# w13_atmega328.net
KiCad netlist of a schematic drawn in EAGLE
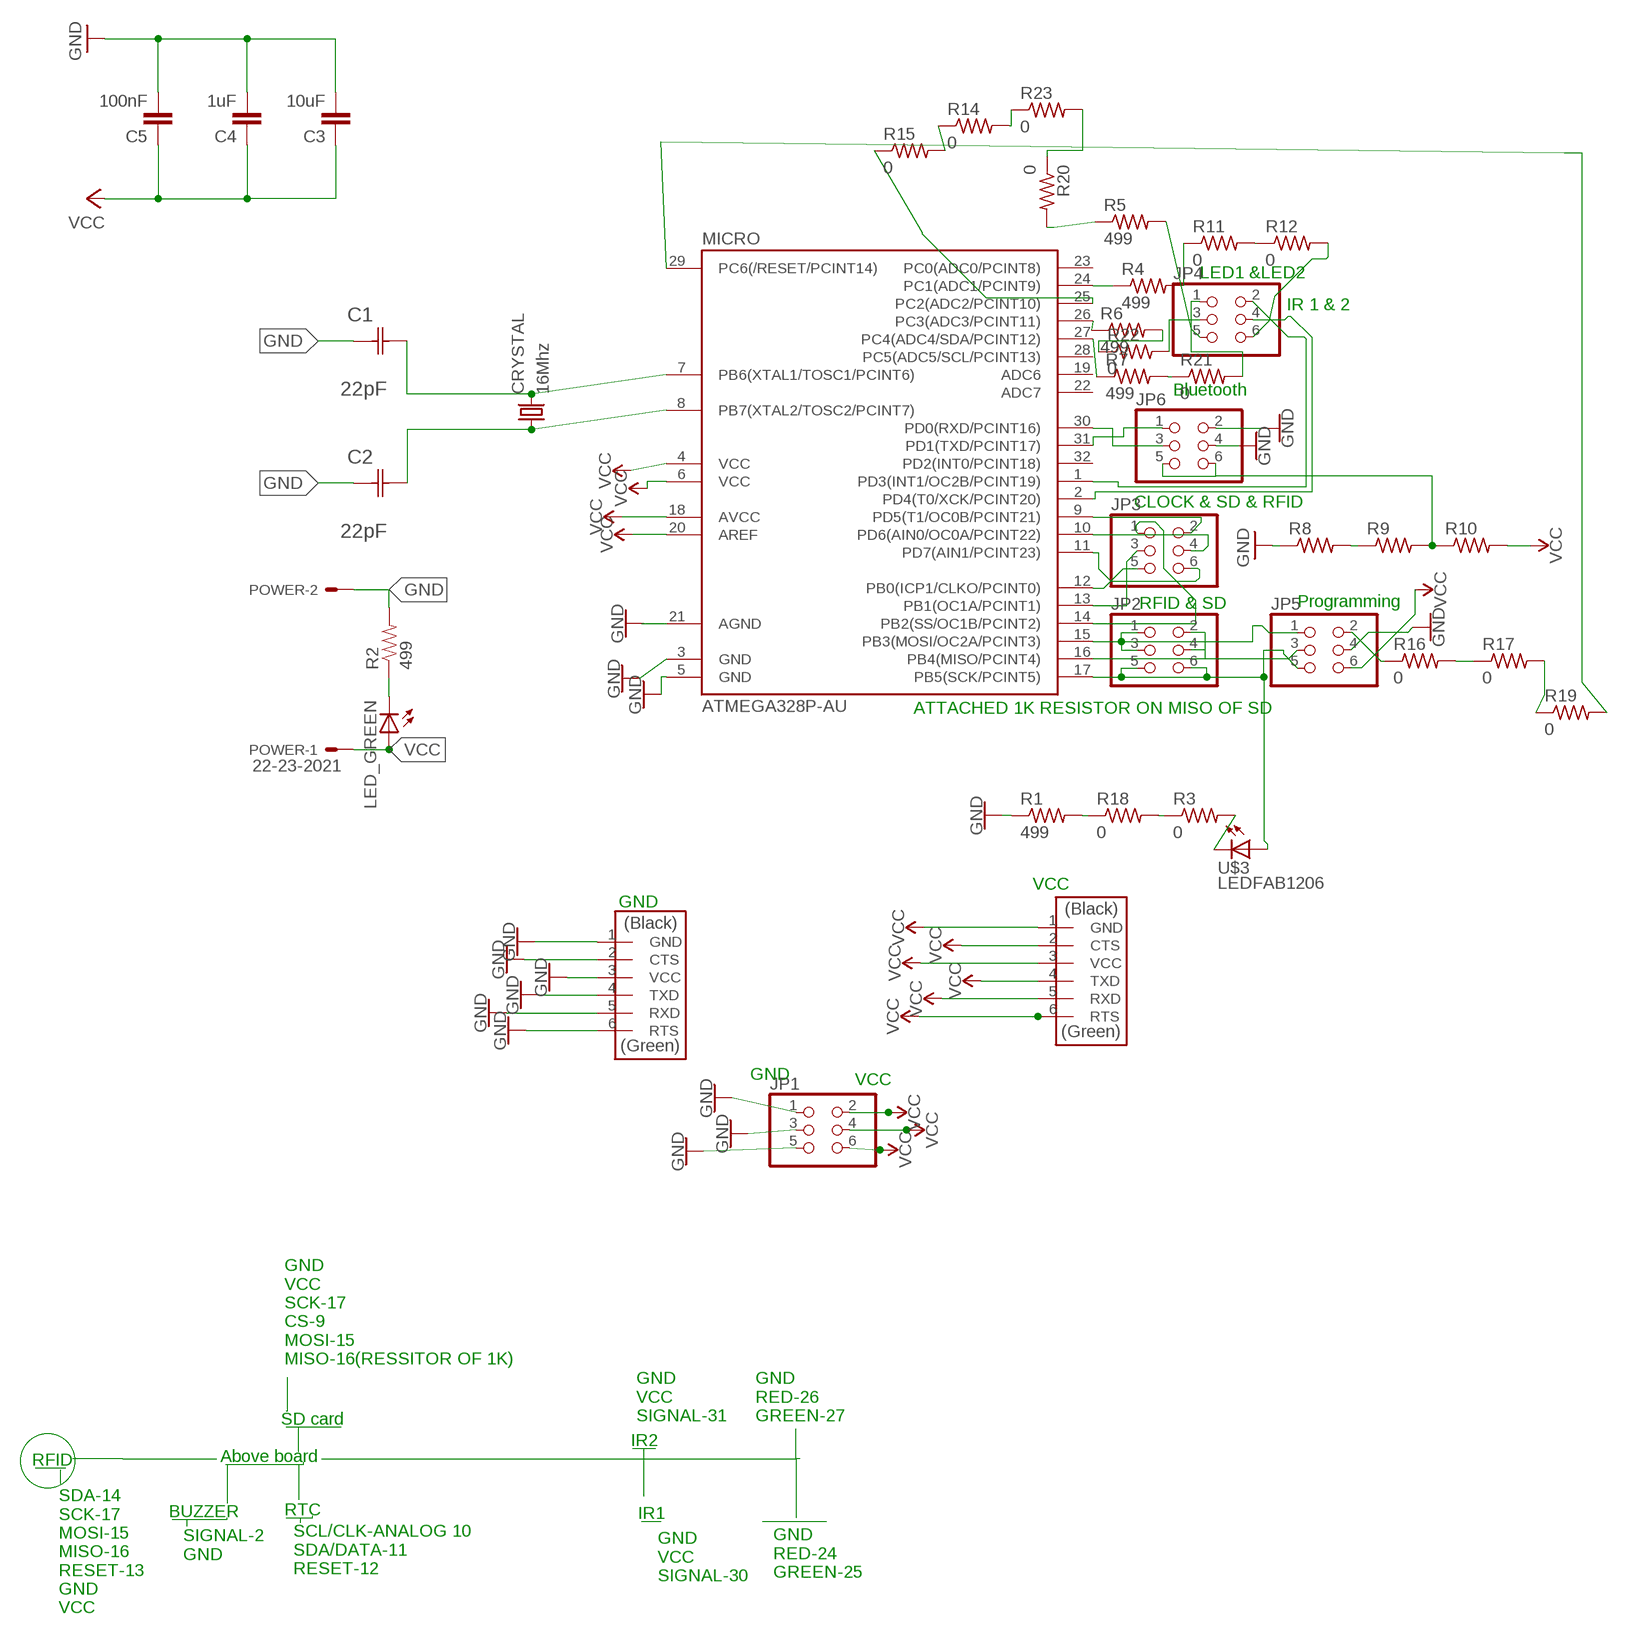
[diagram p0: schematic, sheet 1]

(export (version "E")
  (design (tool "Eeschema 10.0.6"))
  (components
    (comp (ref "C1")
      (value "22pF")
      (footprint "eagle-import:CAPC3216X178N")
      (fields (field (name "MPN") "0612ZC225MAT2A") (field (name "TOLERANCE") "±20%"))
      (libsource (lib "eagle-import") (part "0612ZC225MAT2A"))
    )
    (comp (ref "C2")
      (value "22pF")
      (footprint "eagle-import:CAPC3216X178N")
      (fields (field (name "MPN") "0612ZC225MAT2A") (field (name "TOLERANCE") "±20%"))
      (libsource (lib "eagle-import") (part "0612ZC225MAT2A"))
    )
    (comp (ref "C3")
      (value "10uF")
      (footprint "eagle-import:1206")
      (libsource (lib "eagle-import") (part "CAP1206"))
    )
    (comp (ref "C4")
      (value "1uF")
      (footprint "eagle-import:1206")
      (libsource (lib "eagle-import") (part "CAP1206"))
    )
    (comp (ref "C5")
      (value "100nF")
      (footprint "eagle-import:1206")
      (libsource (lib "eagle-import") (part "CAP1206"))
    )
    (comp (ref "CRYSTAL")
      (value "16Mhz")
      (footprint "eagle-import:CSM-7X-DU")
      (libsource (lib "eagle-import") (part "CSM-7X-DU"))
    )
    (comp (ref "JP1")
      (value "PINHD-2X3-SMD")
      (footprint "eagle-import:2X03SMD")
      (libsource (lib "eagle-import") (part "PINHD-2X3-SMD"))
    )
    (comp (ref "JP2")
      (value "PINHD-2X3-SMD")
      (footprint "eagle-import:2X03SMD")
      (libsource (lib "eagle-import") (part "PINHD-2X3-SMD"))
    )
    (comp (ref "JP3")
      (value "PINHD-2X3-SMD")
      (footprint "eagle-import:2X03SMD")
      (libsource (lib "eagle-import") (part "PINHD-2X3-SMD"))
    )
    (comp (ref "JP4")
      (value "PINHD-2X3-SMD")
      (footprint "eagle-import:2X03SMD")
      (libsource (lib "eagle-import") (part "PINHD-2X3-SMD"))
    )
    (comp (ref "JP5")
      (value "PINHD-2X3-SMD")
      (footprint "eagle-import:2X03SMD")
      (libsource (lib "eagle-import") (part "PINHD-2X3-SMD"))
    )
    (comp (ref "JP6")
      (value "PINHD-2X3-SMD")
      (footprint "eagle-import:2X03SMD")
      (libsource (lib "eagle-import") (part "PINHD-2X3-SMD"))
    )
    (comp (ref "LED_GREEN")
      (value "LED1206")
      (footprint "eagle-import:1206")
      (libsource (lib "eagle-import") (part "LED1206"))
    )
    (comp (ref "MICRO")
      (value "ATMEGA328P-AU")
      (footprint "eagle-import:TQFP32-08")
      (libsource (lib "eagle-import") (part "ATMEGA48/88/168-AU"))
    )
    (comp (ref "POWER")
      (value "22-23-2021")
      (footprint "eagle-import:22-23-2021")
      (fields (field (name "MF") "MOLEX"))
      (libsource (lib "eagle-import") (part "22-23-2021"))
    )
    (comp (ref "R1")
      (value "499")
      (footprint "eagle-import:R1206")
      (libsource (lib "eagle-import") (part "RES-US1206"))
    )
    (comp (ref "R2")
      (value "499")
      (footprint "eagle-import:1206")
      (libsource (lib "eagle-import") (part "RESISTOR1206"))
    )
    (comp (ref "R3")
      (value "0")
      (footprint "eagle-import:R1206FAB")
      (libsource (lib "eagle-import") (part "RES-US1206FAB"))
    )
    (comp (ref "R4")
      (value "499")
      (footprint "eagle-import:R1206FAB")
      (libsource (lib "eagle-import") (part "RES-US1206FAB"))
    )
    (comp (ref "R5")
      (value "499")
      (footprint "eagle-import:R1206FAB")
      (libsource (lib "eagle-import") (part "RES-US1206FAB"))
    )
    (comp (ref "R6")
      (value "499")
      (footprint "eagle-import:R1206FAB")
      (libsource (lib "eagle-import") (part "RES-US1206FAB"))
    )
    (comp (ref "R7")
      (value "499")
      (footprint "eagle-import:R1206FAB")
      (libsource (lib "eagle-import") (part "RES-US1206FAB"))
    )
    (comp (ref "R8")
      (value "RES-US1206FAB")
      (footprint "eagle-import:R1206FAB")
      (libsource (lib "eagle-import") (part "RES-US1206FAB"))
    )
    (comp (ref "R9")
      (value "RES-US1206FAB")
      (footprint "eagle-import:R1206FAB")
      (libsource (lib "eagle-import") (part "RES-US1206FAB"))
    )
    (comp (ref "R10")
      (value "RES-US1206FAB")
      (footprint "eagle-import:R1206FAB")
      (libsource (lib "eagle-import") (part "RES-US1206FAB"))
    )
    (comp (ref "R11")
      (value "0")
      (footprint "eagle-import:R1206FAB")
      (libsource (lib "eagle-import") (part "RES-US1206FAB"))
    )
    (comp (ref "R12")
      (value "0")
      (footprint "eagle-import:R1206FAB")
      (libsource (lib "eagle-import") (part "RES-US1206FAB"))
    )
    (comp (ref "R14")
      (value "0")
      (footprint "eagle-import:R1206FAB")
      (libsource (lib "eagle-import") (part "RES-US1206FAB"))
    )
    (comp (ref "R15")
      (value "0")
      (footprint "eagle-import:R1206FAB")
      (libsource (lib "eagle-import") (part "RES-US1206FAB"))
    )
    (comp (ref "R16")
      (value "0")
      (footprint "eagle-import:R1206FAB")
      (libsource (lib "eagle-import") (part "RES-US1206FAB"))
    )
    (comp (ref "R17")
      (value "0")
      (footprint "eagle-import:R1206FAB")
      (libsource (lib "eagle-import") (part "RES-US1206FAB"))
    )
    (comp (ref "R18")
      (value "0")
      (footprint "eagle-import:R1206FAB")
      (libsource (lib "eagle-import") (part "RES-US1206FAB"))
    )
    (comp (ref "R19")
      (value "0")
      (footprint "eagle-import:R1206FAB")
      (libsource (lib "eagle-import") (part "RES-US1206FAB"))
    )
    (comp (ref "R20")
      (value "0")
      (footprint "eagle-import:R1206FAB")
      (libsource (lib "eagle-import") (part "RES-US1206FAB"))
    )
    (comp (ref "R21")
      (value "0")
      (footprint "eagle-import:R1206FAB")
      (libsource (lib "eagle-import") (part "RES-US1206FAB"))
    )
    (comp (ref "R22")
      (value "0")
      (footprint "eagle-import:R1206FAB")
      (libsource (lib "eagle-import") (part "RES-US1206FAB"))
    )
    (comp (ref "R23")
      (value "0")
      (footprint "eagle-import:R1206FAB")
      (libsource (lib "eagle-import") (part "RES-US1206FAB"))
    )
    (comp (ref "U$1")
      (value "FTDI-SMD-HEADER")
      (footprint "eagle-import:1X06SMD")
      (libsource (lib "eagle-import") (part "FTDI-SMD-HEADER"))
    )
    (comp (ref "U$2")
      (value "FTDI-SMD-HEADER")
      (footprint "eagle-import:1X06SMD")
      (libsource (lib "eagle-import") (part "FTDI-SMD-HEADER"))
    )
    (comp (ref "U$3")
      (value "LEDFAB1206")
      (footprint "eagle-import:LED1206FAB")
      (libsource (lib "eagle-import") (part "LEDFAB1206"))
    )
  )
  (nets
    (net (code "1") (name "GND") (class "Default")
      (node (ref "C1") (pin "1") (pinfunction "C1_1") (pintype "passive"))
      (node (ref "C2") (pin "1") (pinfunction "C1_1") (pintype "passive"))
      (node (ref "C3") (pin "2") (pinfunction "2_2") (pintype "passive"))
      (node (ref "C4") (pin "2") (pinfunction "2_2") (pintype "passive"))
      (node (ref "C5") (pin "2") (pinfunction "2_2") (pintype "passive"))
      (node (ref "JP1") (pin "1") (pinfunction "1_1") (pintype "passive"))
      (node (ref "JP1") (pin "3") (pinfunction "3_3") (pintype "passive"))
      (node (ref "JP1") (pin "5") (pinfunction "5_5") (pintype "passive"))
      (node (ref "JP5") (pin "4") (pinfunction "4_4") (pintype "passive"))
      (node (ref "JP6") (pin "2") (pinfunction "2_2") (pintype "passive"))
      (node (ref "JP6") (pin "4") (pinfunction "4_4") (pintype "passive"))
      (node (ref "MICRO") (pin "3") (pinfunction "GND_3") (pintype "power_in"))
      (node (ref "MICRO") (pin "5") (pinfunction "GND_5") (pintype "power_in"))
      (node (ref "POWER") (pin "2") (pinfunction "S_2") (pintype "passive"))
      (node (ref "R1") (pin "1") (pinfunction "1_1") (pintype "passive"))
      (node (ref "R2") (pin "2") (pinfunction "2_2") (pintype "passive"))
      (node (ref "R8") (pin "1") (pinfunction "1_1") (pintype "passive"))
      (node (ref "U$1") (pin "1") (pinfunction "GND_1") (pintype "bidirectional"))
      (node (ref "U$1") (pin "2") (pinfunction "CTS_2") (pintype "bidirectional"))
      (node (ref "U$1") (pin "3") (pinfunction "VCC_3") (pintype "bidirectional"))
      (node (ref "U$1") (pin "4") (pinfunction "TXD_4") (pintype "bidirectional"))
      (node (ref "U$1") (pin "5") (pinfunction "RXD_5") (pintype "bidirectional"))
      (node (ref "U$1") (pin "6") (pinfunction "RTS_6") (pintype "bidirectional"))
    )
    (net (code "2") (name "Net-(C1-C2)") (class "Default")
      (node (ref "C1") (pin "2") (pinfunction "C2_2") (pintype "passive"))
      (node (ref "CRYSTAL") (pin "2") (pinfunction "2_2") (pintype "passive"))
      (node (ref "MICRO") (pin "7") (pinfunction "PB6(XTAL1/TOSC1/PCINT6)_7") (pintype "bidirectional"))
    )
    (net (code "3") (name "Net-(C2-C2)") (class "Default")
      (node (ref "C2") (pin "2") (pinfunction "C2_2") (pintype "passive"))
      (node (ref "CRYSTAL") (pin "1") (pinfunction "1_1") (pintype "passive"))
      (node (ref "MICRO") (pin "8") (pinfunction "PB7(XTAL2/TOSC2/PCINT7)_8") (pintype "bidirectional"))
    )
    (net (code "4") (name "Net-(JP4-Pad1)") (class "Default")
      (node (ref "JP4") (pin "1") (pinfunction "1_1") (pintype "passive"))
      (node (ref "R21") (pin "2") (pinfunction "2_2") (pintype "passive"))
    )
    (net (code "5") (name "Net-(JP4-Pad3)") (class "Default")
      (node (ref "JP4") (pin "3") (pinfunction "3_3") (pintype "passive"))
      (node (ref "R22") (pin "2") (pinfunction "2_2") (pintype "passive"))
    )
    (net (code "6") (name "Net-(JP4-Pad5)") (class "Default")
      (node (ref "JP4") (pin "5") (pinfunction "5_5") (pintype "passive"))
      (node (ref "R5") (pin "2") (pinfunction "2_2") (pintype "passive"))
    )
    (net (code "7") (name "Net-(JP4-Pad6)") (class "Default")
      (node (ref "JP4") (pin "6") (pinfunction "6_6") (pintype "passive"))
      (node (ref "R12") (pin "2") (pinfunction "2_2") (pintype "passive"))
    )
    (net (code "8") (name "Net-(JP5-Pad2)") (class "Default")
      (node (ref "JP5") (pin "2") (pinfunction "2_2") (pintype "passive"))
      (node (ref "R16") (pin "1") (pinfunction "1_1") (pintype "passive"))
    )
    (net (code "9") (name "Net-(JP6-Pad5)") (class "Default")
      (node (ref "JP6") (pin "5") (pinfunction "5_5") (pintype "passive"))
      (node (ref "JP6") (pin "6") (pinfunction "6_6") (pintype "passive"))
      (node (ref "R10") (pin "1") (pinfunction "1_1") (pintype "passive"))
      (node (ref "R9") (pin "2") (pinfunction "2_2") (pintype "passive"))
    )
    (net (code "10") (name "Net-(LED_GREEN-C)") (class "Default")
      (node (ref "LED_GREEN") (pin "2") (pinfunction "C_2") (pintype "passive"))
      (node (ref "R2") (pin "1") (pinfunction "1_1") (pintype "passive"))
    )
    (net (code "11") (name "Net-(MICRO-PB0(ICP1{slash}CLKO{slash}PCINT0))") (class "Default")
      (node (ref "JP3") (pin "5") (pinfunction "5_5") (pintype "passive"))
      (node (ref "MICRO") (pin "12") (pinfunction "PB0(ICP1/CLKO/PCINT0)_12") (pintype "bidirectional"))
    )
    (net (code "12") (name "Net-(MICRO-PB1(OC1A{slash}PCINT1))") (class "Default")
      (node (ref "JP3") (pin "3") (pinfunction "3_3") (pintype "passive"))
      (node (ref "MICRO") (pin "13") (pinfunction "PB1(OC1A/PCINT1)_13") (pintype "bidirectional"))
    )
    (net (code "13") (name "Net-(MICRO-PB2(SS{slash}OC1B{slash}PCINT2))") (class "Default")
      (node (ref "JP3") (pin "1") (pinfunction "1_1") (pintype "passive"))
      (node (ref "MICRO") (pin "14") (pinfunction "PB2(SS/OC1B/PCINT2)_14") (pintype "bidirectional"))
    )
    (net (code "14") (name "Net-(MICRO-PB3(MOSI{slash}OC2A{slash}PCINT3))") (class "Default")
      (node (ref "JP2") (pin "1") (pinfunction "1_1") (pintype "passive"))
      (node (ref "JP2") (pin "3") (pinfunction "3_3") (pintype "passive"))
      (node (ref "JP5") (pin "1") (pinfunction "1_1") (pintype "passive"))
      (node (ref "MICRO") (pin "15") (pinfunction "PB3(MOSI/OC2A/PCINT3)_15") (pintype "bidirectional"))
    )
    (net (code "15") (name "Net-(MICRO-PB4(MISO{slash}PCINT4))") (class "Default")
      (node (ref "JP2") (pin "2") (pinfunction "2_2") (pintype "passive"))
      (node (ref "JP2") (pin "4") (pinfunction "4_4") (pintype "passive"))
      (node (ref "JP5") (pin "3") (pinfunction "3_3") (pintype "passive"))
      (node (ref "MICRO") (pin "16") (pinfunction "PB4(MISO/PCINT4)_16") (pintype "bidirectional"))
    )
    (net (code "16") (name "Net-(MICRO-PB5(SCK{slash}PCINT5))") (class "Default")
      (node (ref "JP2") (pin "5") (pinfunction "5_5") (pintype "passive"))
      (node (ref "JP2") (pin "6") (pinfunction "6_6") (pintype "passive"))
      (node (ref "JP5") (pin "5") (pinfunction "5_5") (pintype "passive"))
      (node (ref "MICRO") (pin "17") (pinfunction "PB5(SCK/PCINT5)_17") (pintype "bidirectional"))
      (node (ref "U$3") (pin "1") (pinfunction "A_1") (pintype "passive"))
    )
    (net (code "17") (name "Net-(MICRO-PC1(ADC1{slash}PCINT9))") (class "Default")
      (node (ref "MICRO") (pin "24") (pinfunction "PC1(ADC1/PCINT9)_24") (pintype "bidirectional"))
      (node (ref "R4") (pin "1") (pinfunction "1_1") (pintype "passive"))
    )
    (net (code "18") (name "Net-(MICRO-PC2(ADC2{slash}PCINT10))") (class "Default")
      (node (ref "MICRO") (pin "25") (pinfunction "PC2(ADC2/PCINT10)_25") (pintype "bidirectional"))
      (node (ref "R15") (pin "1") (pinfunction "1_1") (pintype "passive"))
    )
    (net (code "19") (name "Net-(MICRO-PC3(ADC3{slash}PCINT11))") (class "Default")
      (node (ref "MICRO") (pin "26") (pinfunction "PC3(ADC3/PCINT11)_26") (pintype "bidirectional"))
      (node (ref "R6") (pin "1") (pinfunction "1_1") (pintype "passive"))
    )
    (net (code "20") (name "Net-(MICRO-PC4(ADC4{slash}SDA{slash}PCINT12))") (class "Default")
      (node (ref "MICRO") (pin "27") (pinfunction "PC4(ADC4/SDA/PCINT12)_27") (pintype "bidirectional"))
      (node (ref "R7") (pin "1") (pinfunction "1_1") (pintype "passive"))
    )
    (net (code "21") (name "Net-(MICRO-PC6({slash}RESET{slash}PCINT14))") (class "Default")
      (node (ref "MICRO") (pin "29") (pinfunction "PC6(/RESET/PCINT14)_29") (pintype "bidirectional"))
      (node (ref "R19") (pin "2") (pinfunction "2_2") (pintype "passive"))
    )
    (net (code "22") (name "Net-(MICRO-PD0(RXD{slash}PCINT16))") (class "Default")
      (node (ref "JP6") (pin "3") (pinfunction "3_3") (pintype "passive"))
      (node (ref "MICRO") (pin "30") (pinfunction "PD0(RXD/PCINT16)_30") (pintype "bidirectional"))
    )
    (net (code "23") (name "Net-(MICRO-PD1(TXD{slash}PCINT17))") (class "Default")
      (node (ref "JP6") (pin "1") (pinfunction "1_1") (pintype "passive"))
      (node (ref "MICRO") (pin "31") (pinfunction "PD1(TXD/PCINT17)_31") (pintype "bidirectional"))
    )
    (net (code "24") (name "Net-(MICRO-PD3(INT1{slash}OC2B{slash}PCINT19))") (class "Default")
      (node (ref "JP4") (pin "2") (pinfunction "2_2") (pintype "passive"))
      (node (ref "MICRO") (pin "1") (pinfunction "PD3(INT1/OC2B/PCINT19)_1") (pintype "bidirectional"))
    )
    (net (code "25") (name "Net-(MICRO-PD4(T0{slash}XCK{slash}PCINT20))") (class "Default")
      (node (ref "JP4") (pin "4") (pinfunction "4_4") (pintype "passive"))
      (node (ref "MICRO") (pin "2") (pinfunction "PD4(T0/XCK/PCINT20)_2") (pintype "bidirectional"))
    )
    (net (code "26") (name "Net-(MICRO-PD5(T1{slash}OC0B{slash}PCINT21))") (class "Default")
      (node (ref "JP3") (pin "2") (pinfunction "2_2") (pintype "passive"))
      (node (ref "MICRO") (pin "9") (pinfunction "PD5(T1/OC0B/PCINT21)_9") (pintype "bidirectional"))
    )
    (net (code "27") (name "Net-(MICRO-PD6(AIN0{slash}OC0A{slash}PCINT22))") (class "Default")
      (node (ref "JP3") (pin "4") (pinfunction "4_4") (pintype "passive"))
      (node (ref "MICRO") (pin "10") (pinfunction "PD6(AIN0/OC0A/PCINT22)_10") (pintype "bidirectional"))
    )
    (net (code "28") (name "Net-(MICRO-PD7(AIN1{slash}PCINT23))") (class "Default")
      (node (ref "JP3") (pin "6") (pinfunction "6_6") (pintype "passive"))
      (node (ref "MICRO") (pin "11") (pinfunction "PD7(AIN1/PCINT23)_11") (pintype "bidirectional"))
    )
    (net (code "29") (name "Net-(R1-Pad2)") (class "Default")
      (node (ref "R1") (pin "2") (pinfunction "2_2") (pintype "passive"))
      (node (ref "R18") (pin "1") (pinfunction "1_1") (pintype "passive"))
    )
    (net (code "30") (name "Net-(R8-Pad2)") (class "Default")
      (node (ref "R8") (pin "2") (pinfunction "2_2") (pintype "passive"))
      (node (ref "R9") (pin "1") (pinfunction "1_1") (pintype "passive"))
    )
    (net (code "31") (name "Net-(R11-Pad1)") (class "Default")
      (node (ref "R11") (pin "1") (pinfunction "1_1") (pintype "passive"))
      (node (ref "R4") (pin "2") (pinfunction "2_2") (pintype "passive"))
    )
    (net (code "32") (name "Net-(R11-Pad2)") (class "Default")
      (node (ref "R11") (pin "2") (pinfunction "2_2") (pintype "passive"))
      (node (ref "R12") (pin "1") (pinfunction "1_1") (pintype "passive"))
    )
    (net (code "33") (name "Net-(R14-Pad1)") (class "Default")
      (node (ref "R14") (pin "1") (pinfunction "1_1") (pintype "passive"))
      (node (ref "R15") (pin "2") (pinfunction "2_2") (pintype "passive"))
    )
    (net (code "34") (name "Net-(R14-Pad2)") (class "Default")
      (node (ref "R14") (pin "2") (pinfunction "2_2") (pintype "passive"))
      (node (ref "R23") (pin "1") (pinfunction "1_1") (pintype "passive"))
    )
    (net (code "35") (name "Net-(R16-Pad2)") (class "Default")
      (node (ref "R16") (pin "2") (pinfunction "2_2") (pintype "passive"))
      (node (ref "R17") (pin "1") (pinfunction "1_1") (pintype "passive"))
    )
    (net (code "36") (name "Net-(R17-Pad2)") (class "Default")
      (node (ref "R17") (pin "2") (pinfunction "2_2") (pintype "passive"))
      (node (ref "R19") (pin "1") (pinfunction "1_1") (pintype "passive"))
    )
    (net (code "37") (name "Net-(R18-Pad2)") (class "Default")
      (node (ref "R18") (pin "2") (pinfunction "2_2") (pintype "passive"))
      (node (ref "R3") (pin "1") (pinfunction "1_1") (pintype "passive"))
    )
    (net (code "38") (name "Net-(R20-Pad1)") (class "Default")
      (node (ref "R20") (pin "1") (pinfunction "1_1") (pintype "passive"))
      (node (ref "R23") (pin "2") (pinfunction "2_2") (pintype "passive"))
    )
    (net (code "39") (name "Net-(R20-Pad2)") (class "Default")
      (node (ref "R20") (pin "2") (pinfunction "2_2") (pintype "passive"))
      (node (ref "R5") (pin "1") (pinfunction "1_1") (pintype "passive"))
    )
    (net (code "40") (name "Net-(R21-Pad1)") (class "Default")
      (node (ref "R21") (pin "1") (pinfunction "1_1") (pintype "passive"))
      (node (ref "R7") (pin "2") (pinfunction "2_2") (pintype "passive"))
    )
    (net (code "41") (name "Net-(R22-Pad1)") (class "Default")
      (node (ref "R22") (pin "1") (pinfunction "1_1") (pintype "passive"))
      (node (ref "R6") (pin "2") (pinfunction "2_2") (pintype "passive"))
    )
    (net (code "42") (name "Net-(U$3-C)") (class "Default")
      (node (ref "R3") (pin "2") (pinfunction "2_2") (pintype "passive"))
      (node (ref "U$3") (pin "2") (pinfunction "C_2") (pintype "passive"))
    )
    (net (code "43") (name "VCC") (class "Default")
      (node (ref "C3") (pin "1") (pinfunction "1_1") (pintype "passive"))
      (node (ref "C4") (pin "1") (pinfunction "1_1") (pintype "passive"))
      (node (ref "C5") (pin "1") (pinfunction "1_1") (pintype "passive"))
      (node (ref "JP1") (pin "2") (pinfunction "2_2") (pintype "passive"))
      (node (ref "JP1") (pin "4") (pinfunction "4_4") (pintype "passive"))
      (node (ref "JP1") (pin "6") (pinfunction "6_6") (pintype "passive"))
      (node (ref "JP5") (pin "6") (pinfunction "6_6") (pintype "passive"))
      (node (ref "LED_GREEN") (pin "1") (pinfunction "A_1") (pintype "passive"))
      (node (ref "MICRO") (pin "18") (pinfunction "AVCC_18") (pintype "passive"))
      (node (ref "MICRO") (pin "20") (pinfunction "AREF_20") (pintype "passive"))
      (node (ref "MICRO") (pin "4") (pinfunction "VCC_4") (pintype "power_in"))
      (node (ref "MICRO") (pin "6") (pinfunction "VCC_6") (pintype "power_in"))
      (node (ref "POWER") (pin "1") (pinfunction "S_1") (pintype "passive"))
      (node (ref "R10") (pin "2") (pinfunction "2_2") (pintype "passive"))
      (node (ref "U$2") (pin "1") (pinfunction "GND_1") (pintype "bidirectional"))
      (node (ref "U$2") (pin "2") (pinfunction "CTS_2") (pintype "bidirectional"))
      (node (ref "U$2") (pin "3") (pinfunction "VCC_3") (pintype "bidirectional"))
      (node (ref "U$2") (pin "4") (pinfunction "TXD_4") (pintype "bidirectional"))
      (node (ref "U$2") (pin "5") (pinfunction "RXD_5") (pintype "bidirectional"))
      (node (ref "U$2") (pin "6") (pinfunction "RTS_6") (pintype "bidirectional"))
    )
    (net (code "44") (name "unconnected-(MICRO-ADC6-Pad19)") (class "Default")
      (node (ref "MICRO") (pin "19") (pinfunction "ADC6_19") (pintype "passive"))
    )
    (net (code "45") (name "unconnected-(MICRO-ADC7-Pad22)") (class "Default")
      (node (ref "MICRO") (pin "22") (pinfunction "ADC7_22") (pintype "passive"))
    )
    (net (code "46") (name "unconnected-(MICRO-AGND-Pad21)") (class "Default")
      (node (ref "MICRO") (pin "21") (pinfunction "AGND_21") (pintype "power_in"))
    )
    (net (code "47") (name "unconnected-(MICRO-PC0(ADC0{slash}PCINT8)-Pad23)") (class "Default")
      (node (ref "MICRO") (pin "23") (pinfunction "PC0(ADC0/PCINT8)_23") (pintype "bidirectional"))
    )
    (net (code "48") (name "unconnected-(MICRO-PC5(ADC5{slash}SCL{slash}PCINT13)-Pad28)") (class "Default")
      (node (ref "MICRO") (pin "28") (pinfunction "PC5(ADC5/SCL/PCINT13)_28") (pintype "bidirectional"))
    )
    (net (code "49") (name "unconnected-(MICRO-PD2(INT0{slash}PCINT18)-Pad32)") (class "Default")
      (node (ref "MICRO") (pin "32") (pinfunction "PD2(INT0/PCINT18)_32") (pintype "bidirectional"))
    )
  )
)
